# UNO_Shield_2021-10-31.net
KiCad netlist of a schematic drawn in Altium Designer
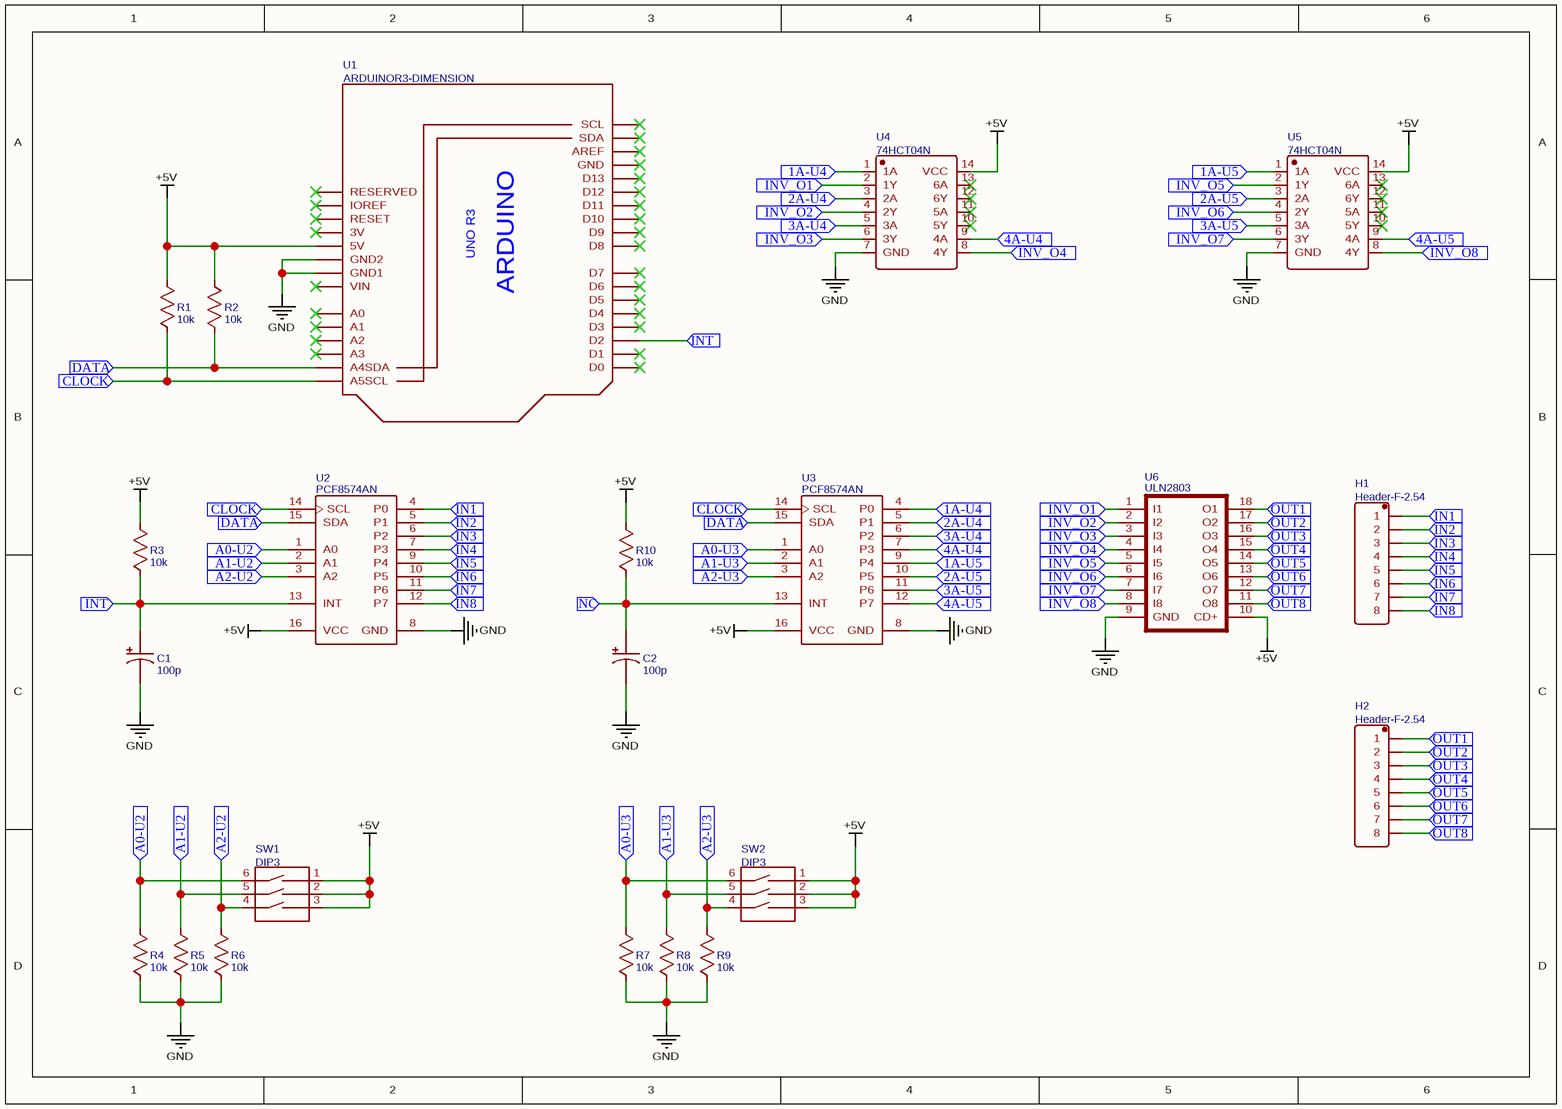
[diagram p0: UNO Shield_2021-10-31.schdoc]

(export (version "E")
  (design (tool "Eeschema 10.0.6"))
  (components
    (comp (ref "C1") (value "100p") (libsource (lib "altium-import") (part "root_0_100p_")))
    (comp (ref "C2") (value "100p") (libsource (lib "altium-import") (part "root_0_100p_")))
    (comp (ref "H1")
      (value "Header-F-2.54")
      (fields
        (field (name "BOM_MANUFACTURER PART") "210S-1*8P L=11.6MMGold-plated black")
        (field (name "BOM_SUPPLIER PART") "C124381")
        (field (name "CONTRIBUTOR") "LCSC")
      )
      (libsource (lib "altium-import") (part "root_2_Header-F-2.54_"))
    )
    (comp (ref "H2")
      (value "Header-F-2.54")
      (fields
        (field (name "BOM_MANUFACTURER PART") "210S-1*8P L=11.6MMGold-plated black")
        (field (name "BOM_SUPPLIER PART") "C124381")
        (field (name "CONTRIBUTOR") "LCSC")
      )
      (libsource (lib "altium-import") (part "root_2_Header-F-2.54_"))
    )
    (comp (ref "R1") (value "10k") (libsource (lib "altium-import") (part "root_1_10k_")))
    (comp (ref "R2") (value "10k") (libsource (lib "altium-import") (part "root_1_10k_")))
    (comp (ref "R3") (value "10k") (libsource (lib "altium-import") (part "root_1_10k_")))
    (comp (ref "R4") (value "10k") (libsource (lib "altium-import") (part "root_1_10k_")))
    (comp (ref "R5") (value "10k") (libsource (lib "altium-import") (part "root_1_10k_")))
    (comp (ref "R6") (value "10k") (libsource (lib "altium-import") (part "root_1_10k_")))
    (comp (ref "R7") (value "10k") (libsource (lib "altium-import") (part "root_1_10k_")))
    (comp (ref "R8") (value "10k") (libsource (lib "altium-import") (part "root_1_10k_")))
    (comp (ref "R9") (value "10k") (libsource (lib "altium-import") (part "root_1_10k_")))
    (comp (ref "R10") (value "10k") (libsource (lib "altium-import") (part "root_1_10k_")))
    (comp (ref "SW1")
      (value "DIP3")
      (fields
        (field (name "BOM_MANUFACTURER PART") "VDG/S-03HG-R")
        (field (name "BOM_SUPPLIER PART") "C52648")
      )
      (libsource (lib "altium-import") (part "root_2_DIP3_"))
    )
    (comp (ref "SW2")
      (value "DIP3")
      (fields
        (field (name "BOM_MANUFACTURER PART") "VDG/S-03HG-R")
        (field (name "BOM_SUPPLIER PART") "C52648")
      )
      (libsource (lib "altium-import") (part "root_2_DIP3_"))
    )
    (comp (ref "U1")
      (value "ARDUINOR3-DIMENSION")
      (fields (field (name "CONTRIBUTOR") "Adafruit"))
      (libsource (lib "altium-import") (part "root_3_ARDUINOR3-DIMENSION_"))
    )
    (comp (ref "U2")
      (value "PCF8574AN")
      (description "Remote 8-Bit IO Expander for I2C-Bus, 2.5 to 6 V, -40 to 85 degC, 16-pin PDIP (N), Pb-Free (RoHS)")
      (libsource (lib "altium-import") (part "root_0_PCF8574AN_"))
    )
    (comp (ref "U3")
      (value "PCF8574AN")
      (description "Remote 8-Bit IO Expander for I2C-Bus, 2.5 to 6 V, -40 to 85 degC, 16-pin PDIP (N), Pb-Free (RoHS)")
      (libsource (lib "altium-import") (part "root_0_PCF8574AN_"))
    )
    (comp (ref "U4") (value "74HCT04N") (libsource (lib "altium-import") (part "root_0_74HCT04N_")))
    (comp (ref "U5") (value "74HCT04N") (libsource (lib "altium-import") (part "root_0_74HCT04N_")))
    (comp (ref "U6")
      (value "ULN2803")
      (fields (field (name "CONTRIBUTOR") "DangerousPrototype"))
      (libsource (lib "altium-import") (part "root_0_ULN2803_"))
    )
  )
  (nets
    (net (code "1") (name "+5V") (class "Default")
      (node (ref "R1") (pin "2") (pinfunction "2_2") (pintype "passive"))
      (node (ref "R10") (pin "2") (pinfunction "2_2") (pintype "passive"))
      (node (ref "R2") (pin "2") (pinfunction "2_2") (pintype "passive"))
      (node (ref "R3") (pin "2") (pinfunction "2_2") (pintype "passive"))
      (node (ref "SW1") (pin "1") (pinfunction "1_1") (pintype "passive"))
      (node (ref "SW1") (pin "2") (pinfunction "2_2") (pintype "passive"))
      (node (ref "SW1") (pin "3") (pinfunction "3_3") (pintype "passive"))
      (node (ref "SW2") (pin "1") (pinfunction "1_1") (pintype "passive"))
      (node (ref "SW2") (pin "2") (pinfunction "2_2") (pintype "passive"))
      (node (ref "SW2") (pin "3") (pinfunction "3_3") (pintype "passive"))
      (node (ref "U1") (pin "5V") (pinfunction "5V_5V") (pintype "passive"))
      (node (ref "U2") (pin "16") (pinfunction "VCC_16") (pintype "passive"))
      (node (ref "U3") (pin "16") (pinfunction "VCC_16") (pintype "passive"))
      (node (ref "U4") (pin "14") (pinfunction "VCC_14") (pintype "passive"))
      (node (ref "U5") (pin "14") (pinfunction "VCC_14") (pintype "passive"))
      (node (ref "U6") (pin "10") (pinfunction "CD+_10") (pintype "passive"))
    )
    (net (code "2") (name "/1A-U4") (class "Default")
      (node (ref "U3") (pin "4") (pinfunction "P0_4") (pintype "passive"))
      (node (ref "U4") (pin "1") (pinfunction "1A_1") (pintype "passive"))
    )
    (net (code "3") (name "/1A-U5") (class "Default")
      (node (ref "U3") (pin "9") (pinfunction "P4_9") (pintype "passive"))
      (node (ref "U5") (pin "1") (pinfunction "1A_1") (pintype "passive"))
    )
    (net (code "4") (name "/2A-U4") (class "Default")
      (node (ref "U3") (pin "5") (pinfunction "P1_5") (pintype "passive"))
      (node (ref "U4") (pin "3") (pinfunction "2A_3") (pintype "passive"))
    )
    (net (code "5") (name "/2A-U5") (class "Default")
      (node (ref "U3") (pin "10") (pinfunction "P5_10") (pintype "passive"))
      (node (ref "U5") (pin "3") (pinfunction "2A_3") (pintype "passive"))
    )
    (net (code "6") (name "/3A-U4") (class "Default")
      (node (ref "U3") (pin "6") (pinfunction "P2_6") (pintype "passive"))
      (node (ref "U4") (pin "5") (pinfunction "3A_5") (pintype "passive"))
    )
    (net (code "7") (name "/3A-U5") (class "Default")
      (node (ref "U3") (pin "11") (pinfunction "P6_11") (pintype "passive"))
      (node (ref "U5") (pin "5") (pinfunction "3A_5") (pintype "passive"))
    )
    (net (code "8") (name "/4A-U4") (class "Default")
      (node (ref "U3") (pin "7") (pinfunction "P3_7") (pintype "passive"))
      (node (ref "U4") (pin "9") (pinfunction "4A_9") (pintype "passive"))
    )
    (net (code "9") (name "/4A-U5") (class "Default")
      (node (ref "U3") (pin "12") (pinfunction "P7_12") (pintype "passive"))
      (node (ref "U5") (pin "9") (pinfunction "4A_9") (pintype "passive"))
    )
    (net (code "10") (name "/A0-U2") (class "Default")
      (node (ref "R4") (pin "2") (pinfunction "2_2") (pintype "passive"))
      (node (ref "SW1") (pin "6") (pinfunction "6_6") (pintype "passive"))
      (node (ref "U2") (pin "1") (pinfunction "A0_1") (pintype "passive"))
    )
    (net (code "11") (name "/A0-U3") (class "Default")
      (node (ref "R7") (pin "2") (pinfunction "2_2") (pintype "passive"))
      (node (ref "SW2") (pin "6") (pinfunction "6_6") (pintype "passive"))
      (node (ref "U3") (pin "1") (pinfunction "A0_1") (pintype "passive"))
    )
    (net (code "12") (name "/A1-U2") (class "Default")
      (node (ref "R5") (pin "2") (pinfunction "2_2") (pintype "passive"))
      (node (ref "SW1") (pin "5") (pinfunction "5_5") (pintype "passive"))
      (node (ref "U2") (pin "2") (pinfunction "A1_2") (pintype "passive"))
    )
    (net (code "13") (name "/A1-U3") (class "Default")
      (node (ref "R8") (pin "2") (pinfunction "2_2") (pintype "passive"))
      (node (ref "SW2") (pin "5") (pinfunction "5_5") (pintype "passive"))
      (node (ref "U3") (pin "2") (pinfunction "A1_2") (pintype "passive"))
    )
    (net (code "14") (name "/A2-U2") (class "Default")
      (node (ref "R6") (pin "2") (pinfunction "2_2") (pintype "passive"))
      (node (ref "SW1") (pin "4") (pinfunction "4_4") (pintype "passive"))
      (node (ref "U2") (pin "3") (pinfunction "A2_3") (pintype "passive"))
    )
    (net (code "15") (name "/A2-U3") (class "Default")
      (node (ref "R9") (pin "2") (pinfunction "2_2") (pintype "passive"))
      (node (ref "SW2") (pin "4") (pinfunction "4_4") (pintype "passive"))
      (node (ref "U3") (pin "3") (pinfunction "A2_3") (pintype "passive"))
    )
    (net (code "16") (name "/CLOCK") (class "Default")
      (node (ref "R1") (pin "1") (pinfunction "1_1") (pintype "passive"))
      (node (ref "U1") (pin "A5") (pinfunction "A5SCL_A5") (pintype "passive"))
      (node (ref "U2") (pin "14") (pinfunction "SCL_14") (pintype "passive"))
      (node (ref "U3") (pin "14") (pinfunction "SCL_14") (pintype "passive"))
    )
    (net (code "17") (name "/DATA") (class "Default")
      (node (ref "R2") (pin "1") (pinfunction "1_1") (pintype "passive"))
      (node (ref "U1") (pin "A4") (pinfunction "A4SDA_A4") (pintype "passive"))
      (node (ref "U2") (pin "15") (pinfunction "SDA_15") (pintype "passive"))
      (node (ref "U3") (pin "15") (pinfunction "SDA_15") (pintype "passive"))
    )
    (net (code "18") (name "/IN1") (class "Default")
      (node (ref "H1") (pin "1") (pinfunction "1_1") (pintype "passive"))
      (node (ref "U2") (pin "4") (pinfunction "P0_4") (pintype "passive"))
    )
    (net (code "19") (name "/IN2") (class "Default")
      (node (ref "H1") (pin "2") (pinfunction "2_2") (pintype "passive"))
      (node (ref "U2") (pin "5") (pinfunction "P1_5") (pintype "passive"))
    )
    (net (code "20") (name "/IN3") (class "Default")
      (node (ref "H1") (pin "3") (pinfunction "3_3") (pintype "passive"))
      (node (ref "U2") (pin "6") (pinfunction "P2_6") (pintype "passive"))
    )
    (net (code "21") (name "/IN4") (class "Default")
      (node (ref "H1") (pin "4") (pinfunction "4_4") (pintype "passive"))
      (node (ref "U2") (pin "7") (pinfunction "P3_7") (pintype "passive"))
    )
    (net (code "22") (name "/IN5") (class "Default")
      (node (ref "H1") (pin "5") (pinfunction "5_5") (pintype "passive"))
      (node (ref "U2") (pin "9") (pinfunction "P4_9") (pintype "passive"))
    )
    (net (code "23") (name "/IN6") (class "Default")
      (node (ref "H1") (pin "6") (pinfunction "6_6") (pintype "passive"))
      (node (ref "U2") (pin "10") (pinfunction "P5_10") (pintype "passive"))
    )
    (net (code "24") (name "/IN7") (class "Default")
      (node (ref "H1") (pin "7") (pinfunction "7_7") (pintype "passive"))
      (node (ref "U2") (pin "11") (pinfunction "P6_11") (pintype "passive"))
    )
    (net (code "25") (name "/IN8") (class "Default")
      (node (ref "H1") (pin "8") (pinfunction "8_8") (pintype "passive"))
      (node (ref "U2") (pin "12") (pinfunction "P7_12") (pintype "passive"))
    )
    (net (code "26") (name "/INT") (class "Default")
      (node (ref "C1") (pin "1") (pinfunction "1_1") (pintype "passive"))
      (node (ref "R3") (pin "1") (pinfunction "1_1") (pintype "passive"))
      (node (ref "U1") (pin "D2") (pinfunction "D2_D2") (pintype "passive"))
      (node (ref "U2") (pin "13") (pinfunction "INT_13") (pintype "passive"))
    )
    (net (code "27") (name "/INV_O1") (class "Default")
      (node (ref "U4") (pin "2") (pinfunction "1Y_2") (pintype "passive"))
      (node (ref "U6") (pin "1") (pinfunction "I1_1") (pintype "passive"))
    )
    (net (code "28") (name "/INV_O2") (class "Default")
      (node (ref "U4") (pin "4") (pinfunction "2Y_4") (pintype "passive"))
      (node (ref "U6") (pin "2") (pinfunction "I2_2") (pintype "passive"))
    )
    (net (code "29") (name "/INV_O3") (class "Default")
      (node (ref "U4") (pin "6") (pinfunction "3Y_6") (pintype "passive"))
      (node (ref "U6") (pin "3") (pinfunction "I3_3") (pintype "passive"))
    )
    (net (code "30") (name "/INV_O4") (class "Default")
      (node (ref "U4") (pin "8") (pinfunction "4Y_8") (pintype "passive"))
      (node (ref "U6") (pin "4") (pinfunction "I4_4") (pintype "passive"))
    )
    (net (code "31") (name "/INV_O5") (class "Default")
      (node (ref "U5") (pin "2") (pinfunction "1Y_2") (pintype "passive"))
      (node (ref "U6") (pin "5") (pinfunction "I5_5") (pintype "passive"))
    )
    (net (code "32") (name "/INV_O6") (class "Default")
      (node (ref "U5") (pin "4") (pinfunction "2Y_4") (pintype "passive"))
      (node (ref "U6") (pin "6") (pinfunction "I6_6") (pintype "passive"))
    )
    (net (code "33") (name "/INV_O7") (class "Default")
      (node (ref "U5") (pin "6") (pinfunction "3Y_6") (pintype "passive"))
      (node (ref "U6") (pin "7") (pinfunction "I7_7") (pintype "passive"))
    )
    (net (code "34") (name "/INV_O8") (class "Default")
      (node (ref "U5") (pin "8") (pinfunction "4Y_8") (pintype "passive"))
      (node (ref "U6") (pin "8") (pinfunction "I8_8") (pintype "passive"))
    )
    (net (code "35") (name "/NC") (class "Default")
      (node (ref "C2") (pin "1") (pinfunction "1_1") (pintype "passive"))
      (node (ref "R10") (pin "1") (pinfunction "1_1") (pintype "passive"))
      (node (ref "U3") (pin "13") (pinfunction "INT_13") (pintype "passive"))
    )
    (net (code "36") (name "/OUT1") (class "Default")
      (node (ref "H2") (pin "1") (pinfunction "1_1") (pintype "passive"))
      (node (ref "U6") (pin "18") (pinfunction "O1_18") (pintype "passive"))
    )
    (net (code "37") (name "/OUT2") (class "Default")
      (node (ref "H2") (pin "2") (pinfunction "2_2") (pintype "passive"))
      (node (ref "U6") (pin "17") (pinfunction "O2_17") (pintype "passive"))
    )
    (net (code "38") (name "/OUT3") (class "Default")
      (node (ref "H2") (pin "3") (pinfunction "3_3") (pintype "passive"))
      (node (ref "U6") (pin "16") (pinfunction "O3_16") (pintype "passive"))
    )
    (net (code "39") (name "/OUT4") (class "Default")
      (node (ref "H2") (pin "4") (pinfunction "4_4") (pintype "passive"))
      (node (ref "U6") (pin "15") (pinfunction "O4_15") (pintype "passive"))
    )
    (net (code "40") (name "/OUT5") (class "Default")
      (node (ref "H2") (pin "5") (pinfunction "5_5") (pintype "passive"))
      (node (ref "U6") (pin "14") (pinfunction "O5_14") (pintype "passive"))
    )
    (net (code "41") (name "/OUT6") (class "Default")
      (node (ref "H2") (pin "6") (pinfunction "6_6") (pintype "passive"))
      (node (ref "U6") (pin "13") (pinfunction "O6_13") (pintype "passive"))
    )
    (net (code "42") (name "/OUT7") (class "Default")
      (node (ref "H2") (pin "7") (pinfunction "7_7") (pintype "passive"))
      (node (ref "U6") (pin "12") (pinfunction "O7_12") (pintype "passive"))
    )
    (net (code "43") (name "/OUT8") (class "Default")
      (node (ref "H2") (pin "8") (pinfunction "8_8") (pintype "passive"))
      (node (ref "U6") (pin "11") (pinfunction "O8_11") (pintype "passive"))
    )
    (net (code "44") (name "GND") (class "Default")
      (node (ref "C1") (pin "2") (pinfunction "2_2") (pintype "passive"))
      (node (ref "C2") (pin "2") (pinfunction "2_2") (pintype "passive"))
      (node (ref "R4") (pin "1") (pinfunction "1_1") (pintype "passive"))
      (node (ref "R5") (pin "1") (pinfunction "1_1") (pintype "passive"))
      (node (ref "R6") (pin "1") (pinfunction "1_1") (pintype "passive"))
      (node (ref "R7") (pin "1") (pinfunction "1_1") (pintype "passive"))
      (node (ref "R8") (pin "1") (pinfunction "1_1") (pintype "passive"))
      (node (ref "R9") (pin "1") (pinfunction "1_1") (pintype "passive"))
      (node (ref "U1") (pin "GND1") (pinfunction "GND1_GND1") (pintype "passive"))
      (node (ref "U1") (pin "GND2") (pinfunction "GND2_GND2") (pintype "passive"))
      (node (ref "U2") (pin "8") (pinfunction "GND_8") (pintype "passive"))
      (node (ref "U3") (pin "8") (pinfunction "GND_8") (pintype "passive"))
      (node (ref "U4") (pin "7") (pinfunction "GND_7") (pintype "passive"))
      (node (ref "U5") (pin "7") (pinfunction "GND_7") (pintype "passive"))
      (node (ref "U6") (pin "9") (pinfunction "GND_9") (pintype "passive"))
    )
    (net (code "45") (name "unconnected-(U1-Pad3V)") (class "Default")
      (node (ref "U1") (pin "3V") (pinfunction "3V_3V") (pintype "passive+no_connect"))
    )
    (net (code "46") (name "unconnected-(U1-PadA0)") (class "Default")
      (node (ref "U1") (pin "A0") (pinfunction "A0_A0") (pintype "passive+no_connect"))
    )
    (net (code "47") (name "unconnected-(U1-PadA1)") (class "Default")
      (node (ref "U1") (pin "A1") (pinfunction "A1_A1") (pintype "passive+no_connect"))
    )
    (net (code "48") (name "unconnected-(U1-PadA2)") (class "Default")
      (node (ref "U1") (pin "A2") (pinfunction "A2_A2") (pintype "passive+no_connect"))
    )
    (net (code "49") (name "unconnected-(U1-PadA3)") (class "Default")
      (node (ref "U1") (pin "A3") (pinfunction "A3_A3") (pintype "passive+no_connect"))
    )
    (net (code "50") (name "unconnected-(U1-PadAREF)") (class "Default")
      (node (ref "U1") (pin "AREF") (pinfunction "AREF_AREF") (pintype "passive+no_connect"))
    )
    (net (code "51") (name "unconnected-(U1-PadD0)") (class "Default")
      (node (ref "U1") (pin "D0") (pinfunction "D0_D0") (pintype "passive+no_connect"))
    )
    (net (code "52") (name "unconnected-(U1-PadD1)") (class "Default")
      (node (ref "U1") (pin "D1") (pinfunction "D1_D1") (pintype "passive+no_connect"))
    )
    (net (code "53") (name "unconnected-(U1-PadD3)") (class "Default")
      (node (ref "U1") (pin "D3") (pinfunction "D3_D3") (pintype "passive+no_connect"))
    )
    (net (code "54") (name "unconnected-(U1-PadD4)") (class "Default")
      (node (ref "U1") (pin "D4") (pinfunction "D4_D4") (pintype "passive+no_connect"))
    )
    (net (code "55") (name "unconnected-(U1-PadD5)") (class "Default")
      (node (ref "U1") (pin "D5") (pinfunction "D5_D5") (pintype "passive+no_connect"))
    )
    (net (code "56") (name "unconnected-(U1-PadD6)") (class "Default")
      (node (ref "U1") (pin "D6") (pinfunction "D6_D6") (pintype "passive+no_connect"))
    )
    (net (code "57") (name "unconnected-(U1-PadD7)") (class "Default")
      (node (ref "U1") (pin "D7") (pinfunction "D7_D7") (pintype "passive+no_connect"))
    )
    (net (code "58") (name "unconnected-(U1-PadD8)") (class "Default")
      (node (ref "U1") (pin "D8") (pinfunction "D8_D8") (pintype "passive+no_connect"))
    )
    (net (code "59") (name "unconnected-(U1-PadD9)") (class "Default")
      (node (ref "U1") (pin "D9") (pinfunction "D9_D9") (pintype "passive+no_connect"))
    )
    (net (code "60") (name "unconnected-(U1-PadD10)") (class "Default")
      (node (ref "U1") (pin "D10") (pinfunction "D10_D10") (pintype "passive+no_connect"))
    )
    (net (code "61") (name "unconnected-(U1-PadD11)") (class "Default")
      (node (ref "U1") (pin "D11") (pinfunction "D11_D11") (pintype "passive+no_connect"))
    )
    (net (code "62") (name "unconnected-(U1-PadD12)") (class "Default")
      (node (ref "U1") (pin "D12") (pinfunction "D12_D12") (pintype "passive+no_connect"))
    )
    (net (code "63") (name "unconnected-(U1-PadD13)") (class "Default")
      (node (ref "U1") (pin "D13") (pinfunction "D13_D13") (pintype "passive+no_connect"))
    )
    (net (code "64") (name "unconnected-(U1-PadGND)") (class "Default")
      (node (ref "U1") (pin "GND") (pinfunction "GND_GND") (pintype "passive+no_connect"))
    )
    (net (code "65") (name "unconnected-(U1-PadIOREF)") (class "Default")
      (node (ref "U1") (pin "IOREF") (pinfunction "IOREF_IOREF") (pintype "passive+no_connect"))
    )
    (net (code "66") (name "unconnected-(U1-PadRESERVED)") (class "Default")
      (node (ref "U1") (pin "RESERVED") (pinfunction "RESERVED_RESERVED") (pintype "passive+no_connect"))
    )
    (net (code "67") (name "unconnected-(U1-PadRESET)") (class "Default")
      (node (ref "U1") (pin "RESET") (pinfunction "RESET_RESET") (pintype "passive+no_connect"))
    )
    (net (code "68") (name "unconnected-(U1-PadSCL)") (class "Default")
      (node (ref "U1") (pin "SCL") (pinfunction "SCL_SCL") (pintype "passive+no_connect"))
    )
    (net (code "69") (name "unconnected-(U1-PadSDA)") (class "Default")
      (node (ref "U1") (pin "SDA") (pinfunction "SDA_SDA") (pintype "passive+no_connect"))
    )
    (net (code "70") (name "unconnected-(U1-PadVIN)") (class "Default")
      (node (ref "U1") (pin "VIN") (pinfunction "VIN_VIN") (pintype "passive+no_connect"))
    )
    (net (code "71") (name "unconnected-(U4-5A-Pad11)") (class "Default")
      (node (ref "U4") (pin "11") (pinfunction "5A_11") (pintype "passive+no_connect"))
    )
    (net (code "72") (name "unconnected-(U4-5Y-Pad10)") (class "Default")
      (node (ref "U4") (pin "10") (pinfunction "5Y_10") (pintype "passive+no_connect"))
    )
    (net (code "73") (name "unconnected-(U4-6A-Pad13)") (class "Default")
      (node (ref "U4") (pin "13") (pinfunction "6A_13") (pintype "passive+no_connect"))
    )
    (net (code "74") (name "unconnected-(U4-6Y-Pad12)") (class "Default")
      (node (ref "U4") (pin "12") (pinfunction "6Y_12") (pintype "passive+no_connect"))
    )
    (net (code "75") (name "unconnected-(U5-5A-Pad11)") (class "Default")
      (node (ref "U5") (pin "11") (pinfunction "5A_11") (pintype "passive+no_connect"))
    )
    (net (code "76") (name "unconnected-(U5-5Y-Pad10)") (class "Default")
      (node (ref "U5") (pin "10") (pinfunction "5Y_10") (pintype "passive+no_connect"))
    )
    (net (code "77") (name "unconnected-(U5-6A-Pad13)") (class "Default")
      (node (ref "U5") (pin "13") (pinfunction "6A_13") (pintype "passive+no_connect"))
    )
    (net (code "78") (name "unconnected-(U5-6Y-Pad12)") (class "Default")
      (node (ref "U5") (pin "12") (pinfunction "6Y_12") (pintype "passive+no_connect"))
    )
  )
)
